# Microcontroller.net
KiCad netlist of a schematic drawn in Altium Designer
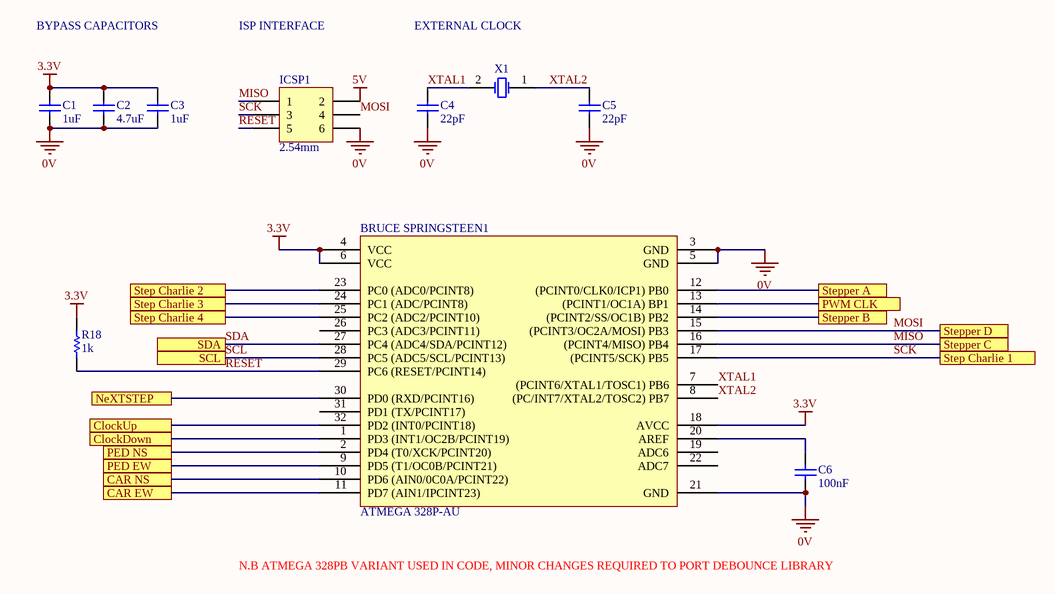
[diagram p0: Microcontroller.SchDoc]

(export (version "E")
  (design (tool "Eeschema 10.0.6"))
  (components
    (comp (ref "BRUCE SPRINGSTEEN1")
      (value "ATMEGA 328P-AU")
      (footprint "ATMEL TQFP-32")
      (description "AVR AVR® ATmega Microcontroller IC 8-Bit 20MHz 32KB (16K x 16) FLASH 32-TQFP (7x7)")
      (fields (field (name "MANUFACTURER") "ATMEL") (field (name "DIGIKEY PART NUMBER") "ATMEGA328P-AU-ND"))
      (libsource (lib "ts_19-standard-library-IED") (part "ATMEGA 328P-AU"))
    )
    (comp (ref "C1")
      (value "1uF")
      (footprint "0805")
      (fields
        (field (name "PART NUMBER") "GCM21BR71A105KA37L")
        (field (name "TOLERANCE") "10%")
        (field (name "MANUFACTURER") "muRata")
      )
      (libsource (lib "ts_19-standard-library-IED") (part "Capacitor"))
    )
    (comp (ref "C2")
      (value "4.7uF")
      (footprint "0805")
      (fields
        (field (name "PART NUMBER") "GCM21BR61A475KA37L")
        (field (name "TOLERANCE") "10%")
        (field (name "MANUFACTURER") "muRata")
      )
      (libsource (lib "ts_19-standard-library-IED") (part "Capacitor"))
    )
    (comp (ref "C3")
      (value "1uF")
      (footprint "0805")
      (fields
        (field (name "PART NUMBER") "GCM21BR71A105KA37L")
        (field (name "TOLERANCE") "10%")
        (field (name "MANUFACTURER") "muRata")
      )
      (libsource (lib "ts_19-standard-library-IED") (part "Capacitor"))
    )
    (comp (ref "C4")
      (value "22pF")
      (footprint "0805")
      (fields
        (field (name "PART NUMBER") "GCM21B5C1H220JA37L")
        (field (name "TOLERANCE") "5%")
        (field (name "MANUFACTURER") "muRata")
      )
      (libsource (lib "ts_19-standard-library-IED") (part "Capacitor"))
    )
    (comp (ref "C5")
      (value "22pF")
      (footprint "0805")
      (fields
        (field (name "PART NUMBER") "GCM21B5C1H220JA37L")
        (field (name "TOLERANCE") "5%")
        (field (name "MANUFACTURER") "muRata")
      )
      (libsource (lib "ts_19-standard-library-IED") (part "Capacitor"))
    )
    (comp (ref "C6")
      (value "100nF")
      (footprint "0805")
      (fields
        (field (name "PART NUMBER") "GCM21BR71E104KA37L")
        (field (name "TOLERANCE") "10%")
        (field (name "MANUFACTURER") "muRata")
      )
      (libsource (lib "ts_19-standard-library-IED") (part "Capacitor"))
    )
    (comp (ref "ICSP1")
      (value "2.54mm")
      (footprint "Header 2x3")
      (fields (field (name "PART NUMBER") "Header 2x3") (field (name "CONTACT") "NA"))
      (libsource (lib "ts_19-standard-connectors-IED") (part "Header 2x3"))
    )
    (comp (ref "R18")
      (value "1k")
      (footprint "0805")
      (fields
        (field (name "MANUFACTURER") "YAGEO")
        (field (name "PART NUMBER") "RC0805FR071KL")
        (field (name "TOLERANCE") "0.01")
      )
      (libsource (lib "ts_19-standard-library-IED") (part "Resistor"))
    )
    (comp (ref "X1")
      (value "~")
      (footprint "Abracon HC-49/US")
      (fields
        (field (name "MANUFACTURER") "Abracon LLC")
        (field (name "PART NUMBER") "ABLS-16.000MHZ-B4-T")
        (field (name "DIGIKEY PART NUMBER") "535-10226-1-ND")
      )
      (libsource (lib "ts_19-standard-library") (part "Crystal"))
    )
  )
  (nets
    (net (code "1") (name "/CAR EW") (class "Default")
      (node (ref "BRUCE SPRINGSTEEN1") (pin "11") (pinfunction "PD7_(AIN1/IPCINT23)_11") (pintype "passive"))
    )
    (net (code "2") (name "/CAR NS") (class "Default")
      (node (ref "BRUCE SPRINGSTEEN1") (pin "10") (pinfunction "PD6_(AIN0/0C0A/PCINT22)_10") (pintype "passive"))
    )
    (net (code "3") (name "/ClockDown") (class "Default")
      (node (ref "BRUCE SPRINGSTEEN1") (pin "1") (pinfunction "PD3_(INT1/OC2B/PCINT19)_1") (pintype "passive"))
    )
    (net (code "4") (name "/ClockUp") (class "Default")
      (node (ref "BRUCE SPRINGSTEEN1") (pin "32") (pinfunction "PD2_(INT0/PCINT18)_32") (pintype "passive"))
    )
    (net (code "5") (name "/MISO") (class "Default")
      (node (ref "BRUCE SPRINGSTEEN1") (pin "16") (pinfunction "(PCINT4/MISO)_PB4_16") (pintype "passive"))
      (node (ref "ICSP1") (pin "1") (pinfunction "1_1") (pintype "passive"))
    )
    (net (code "6") (name "/MOSI") (class "Default")
      (node (ref "BRUCE SPRINGSTEEN1") (pin "15") (pinfunction "(PCINT3/OC2A/MOSI)_PB3_15") (pintype "passive"))
      (node (ref "ICSP1") (pin "4") (pinfunction "4_4") (pintype "passive"))
    )
    (net (code "7") (name "/NeXTSTEP") (class "Default")
      (node (ref "BRUCE SPRINGSTEEN1") (pin "30") (pinfunction "PD0_(RXD/PCINT16)_30") (pintype "passive"))
    )
    (net (code "8") (name "/PED EW") (class "Default")
      (node (ref "BRUCE SPRINGSTEEN1") (pin "9") (pinfunction "PD5_(T1/OC0B/PCINT21)_9") (pintype "passive"))
    )
    (net (code "9") (name "/PED NS") (class "Default")
      (node (ref "BRUCE SPRINGSTEEN1") (pin "2") (pinfunction "PD4_(T0/XCK/PCINT20)_2") (pintype "passive"))
    )
    (net (code "10") (name "/PWM CLK") (class "Default")
      (node (ref "BRUCE SPRINGSTEEN1") (pin "13") (pinfunction "(PCINT1/OC1A)_BP1_13") (pintype "passive"))
    )
    (net (code "11") (name "/RESET") (class "Default")
      (node (ref "BRUCE SPRINGSTEEN1") (pin "29") (pinfunction "PC6_(RESET/PCINT14)_29") (pintype "passive"))
      (node (ref "ICSP1") (pin "5") (pinfunction "5_5") (pintype "passive"))
      (node (ref "R18") (pin "1") (pinfunction "1_1") (pintype "passive"))
    )
    (net (code "12") (name "/SCK") (class "Default")
      (node (ref "BRUCE SPRINGSTEEN1") (pin "17") (pinfunction "(PCINT5/SCK)_PB5_17") (pintype "passive"))
      (node (ref "ICSP1") (pin "3") (pinfunction "3_3") (pintype "passive"))
    )
    (net (code "13") (name "/SCL") (class "Default")
      (node (ref "BRUCE SPRINGSTEEN1") (pin "28") (pinfunction "PC5_(ADC5/SCL/PCINT13)_28") (pintype "passive"))
    )
    (net (code "14") (name "/SDA") (class "Default")
      (node (ref "BRUCE SPRINGSTEEN1") (pin "27") (pinfunction "PC4_(ADC4/SDA/PCINT12)_27") (pintype "passive"))
    )
    (net (code "15") (name "/Step Charlie 2") (class "Default")
      (node (ref "BRUCE SPRINGSTEEN1") (pin "23") (pinfunction "PC0_(ADC0/PCINT8)_23") (pintype "passive"))
    )
    (net (code "16") (name "/Step Charlie 3") (class "Default")
      (node (ref "BRUCE SPRINGSTEEN1") (pin "24") (pinfunction "PC1_(ADC/PCINT8)_24") (pintype "passive"))
    )
    (net (code "17") (name "/Step Charlie 4") (class "Default")
      (node (ref "BRUCE SPRINGSTEEN1") (pin "25") (pinfunction "PC2_(ADC2/PCINT10)_25") (pintype "passive"))
    )
    (net (code "18") (name "/Stepper A") (class "Default")
      (node (ref "BRUCE SPRINGSTEEN1") (pin "12") (pinfunction "(PCINT0/CLK0/ICP1)_PB0_12") (pintype "passive"))
    )
    (net (code "19") (name "/Stepper B") (class "Default")
      (node (ref "BRUCE SPRINGSTEEN1") (pin "14") (pinfunction "(PCINT2/SS/OC1B)_PB2_14") (pintype "passive"))
    )
    (net (code "20") (name "/XTAL1") (class "Default")
      (node (ref "BRUCE SPRINGSTEEN1") (pin "7") (pinfunction "(PCINT6/XTAL1/TOSC1)_PB6_7") (pintype "passive"))
      (node (ref "C4") (pin "2") (pinfunction "2_2") (pintype "passive"))
      (node (ref "X1") (pin "2") (pinfunction "OSC2_2") (pintype "passive"))
    )
    (net (code "21") (name "/XTAL2") (class "Default")
      (node (ref "BRUCE SPRINGSTEEN1") (pin "8") (pinfunction "(PC/INT7/XTAL2/TOSC2)_PB7_8") (pintype "passive"))
      (node (ref "C5") (pin "2") (pinfunction "2_2") (pintype "passive"))
      (node (ref "X1") (pin "1") (pinfunction "OSC1_1") (pintype "passive"))
    )
    (net (code "22") (name "0V") (class "Default")
      (node (ref "BRUCE SPRINGSTEEN1") (pin "21") (pinfunction "GND_21") (pintype "passive"))
      (node (ref "BRUCE SPRINGSTEEN1") (pin "3") (pinfunction "GND_3") (pintype "passive"))
      (node (ref "BRUCE SPRINGSTEEN1") (pin "5") (pinfunction "GND_5") (pintype "passive"))
      (node (ref "C1") (pin "1") (pinfunction "1_1") (pintype "passive"))
      (node (ref "C2") (pin "1") (pinfunction "1_1") (pintype "passive"))
      (node (ref "C3") (pin "1") (pinfunction "1_1") (pintype "passive"))
      (node (ref "C4") (pin "1") (pinfunction "1_1") (pintype "passive"))
      (node (ref "C5") (pin "1") (pinfunction "1_1") (pintype "passive"))
      (node (ref "C6") (pin "1") (pinfunction "1_1") (pintype "passive"))
      (node (ref "ICSP1") (pin "6") (pinfunction "6_6") (pintype "passive"))
    )
    (net (code "23") (name "3.3V") (class "Default")
      (node (ref "BRUCE SPRINGSTEEN1") (pin "18") (pinfunction "AVCC_18") (pintype "passive"))
      (node (ref "BRUCE SPRINGSTEEN1") (pin "4") (pinfunction "VCC_4") (pintype "passive"))
      (node (ref "BRUCE SPRINGSTEEN1") (pin "6") (pinfunction "VCC_6") (pintype "passive"))
      (node (ref "C1") (pin "2") (pinfunction "2_2") (pintype "passive"))
      (node (ref "C2") (pin "2") (pinfunction "2_2") (pintype "passive"))
      (node (ref "C3") (pin "2") (pinfunction "2_2") (pintype "passive"))
      (node (ref "R18") (pin "2") (pinfunction "2_2") (pintype "passive"))
    )
    (net (code "24") (name "5V") (class "Default")
      (node (ref "ICSP1") (pin "2") (pinfunction "2_2") (pintype "passive"))
    )
    (net (code "25") (name "Net-(BRUCE SPRINGSTEEN1-AREF)") (class "Default")
      (node (ref "BRUCE SPRINGSTEEN1") (pin "20") (pinfunction "AREF_20") (pintype "passive"))
      (node (ref "C6") (pin "2") (pinfunction "2_2") (pintype "passive"))
    )
    (net (code "26") (name "unconnected-(BRUCE SPRINGSTEEN1-ADC6-Pad19)") (class "Default")
      (node (ref "BRUCE SPRINGSTEEN1") (pin "19") (pinfunction "ADC6_19") (pintype "passive"))
    )
    (net (code "27") (name "unconnected-(BRUCE SPRINGSTEEN1-ADC7-Pad22)") (class "Default")
      (node (ref "BRUCE SPRINGSTEEN1") (pin "22") (pinfunction "ADC7_22") (pintype "passive"))
    )
    (net (code "28") (name "unconnected-(BRUCE SPRINGSTEEN1-PC3_(ADC3{slash}PCINT11)-Pad26)") (class "Default")
      (node (ref "BRUCE SPRINGSTEEN1") (pin "26") (pinfunction "PC3_(ADC3/PCINT11)_26") (pintype "passive"))
    )
    (net (code "29") (name "unconnected-(BRUCE SPRINGSTEEN1-PD1_(TX{slash}PCINT17)-Pad31)") (class "Default")
      (node (ref "BRUCE SPRINGSTEEN1") (pin "31") (pinfunction "PD1_(TX/PCINT17)_31") (pintype "passive"))
    )
  )
)
